# USB_Power.net
KiCad netlist of a schematic drawn in Altium Designer
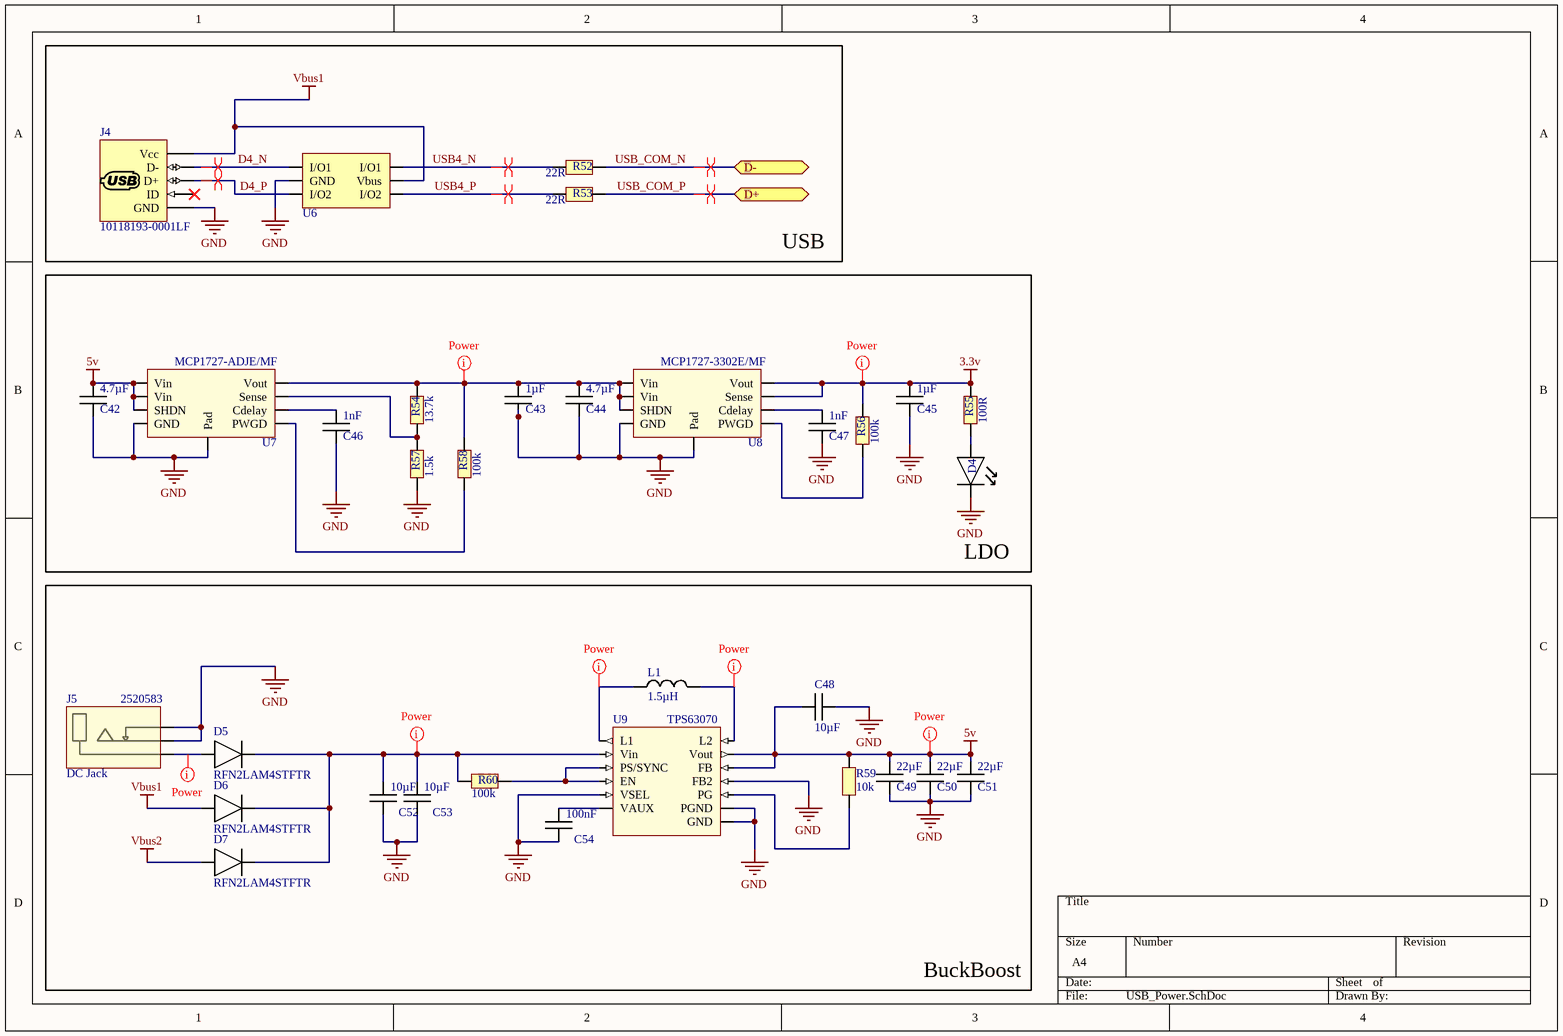
[diagram p0: USB_Power.SchDoc]

(export (version "E")
  (design (tool "Eeschema 10.0.6"))
  (components
    (comp (ref "C42")
      (value "4.7µF")
      (footprint "0603")
      (libsource (lib "Carte_design_SCHLib") (part "Capa"))
    )
    (comp (ref "C43") (value "1µF") (footprint "0603") (libsource (lib "Carte_design_SCHLib") (part "Capa")))
    (comp (ref "C44")
      (value "4.7µF")
      (footprint "0603")
      (libsource (lib "Carte_design_SCHLib") (part "Capa"))
    )
    (comp (ref "C45") (value "1µF") (footprint "0603") (libsource (lib "Carte_design_SCHLib") (part "Capa")))
    (comp (ref "C46") (value "1nF") (footprint "0603") (libsource (lib "Carte_design_SCHLib") (part "Capa")))
    (comp (ref "C47") (value "1nF") (footprint "0603") (libsource (lib "Carte_design_SCHLib") (part "Capa")))
    (comp (ref "C48") (value "10µF") (footprint "0603") (libsource (lib "Carte_design_SCHLib") (part "Capa")))
    (comp (ref "C49") (value "22µF") (footprint "0603") (libsource (lib "Carte_design_SCHLib") (part "Capa")))
    (comp (ref "C50") (value "22µF") (footprint "0603") (libsource (lib "Carte_design_SCHLib") (part "Capa")))
    (comp (ref "C51") (value "22µF") (footprint "0603") (libsource (lib "Carte_design_SCHLib") (part "Capa")))
    (comp (ref "C52") (value "10µF") (footprint "0603") (libsource (lib "Carte_design_SCHLib") (part "Capa")))
    (comp (ref "C53") (value "10µF") (footprint "0603") (libsource (lib "Carte_design_SCHLib") (part "Capa")))
    (comp (ref "C54")
      (value "100nF")
      (footprint "0603")
      (libsource (lib "Carte_design_SCHLib") (part "Capa"))
    )
    (comp (ref "D4")
      (value "Led")
      (footprint "LED_0603")
      (libsource (lib "Carte_design_SCHLib") (part "Led"))
    )
    (comp (ref "D5")
      (value "RFN2LAM4STFTR")
      (footprint "LEd_Pilou")
      (description "RFN2LAM4STF IS THE HIGH RELIABIL")
      (libsource (lib "Carte_design_SCHLib") (part "RFN2LAM4STFTR"))
    )
    (comp (ref "D6")
      (value "RFN2LAM4STFTR")
      (footprint "LEd_Pilou")
      (description "RFN2LAM4STF IS THE HIGH RELIABIL")
      (libsource (lib "Carte_design_SCHLib") (part "RFN2LAM4STFTR"))
    )
    (comp (ref "D7")
      (value "RFN2LAM4STFTR")
      (footprint "LEd_Pilou")
      (description "RFN2LAM4STF IS THE HIGH RELIABIL")
      (libsource (lib "Carte_design_SCHLib") (part "RFN2LAM4STFTR"))
    )
    (comp (ref "J4")
      (value "10118193-0001LF")
      (footprint "Mini_USB_mixte")
      (description "CONN RCPT USB2.0 MICRO B SMD R/A")
      (libsource (lib "Carte_design_SCHLib") (part "10118193-0001LF"))
    )
    (comp (ref "J5")
      (value "DC Jack")
      (footprint "Jack")
      (fields (field (name "SUPPLIER PART NUMBER 1") "2520583"))
      (libsource (lib "Carte_design_SCHLib") (part "Jack"))
    )
    (comp (ref "L1")
      (value "1.5µH")
      (footprint "self_alim")
      (fields (field (name "TOLERANCE") "20%"))
      (libsource (lib "Carte_design_SCHLib") (part "self_alim"))
    )
    (comp (ref "R52") (value "22R") (footprint "0603") (libsource (lib "") (part "Resistance_1")))
    (comp (ref "R53") (value "22R") (footprint "0603") (libsource (lib "") (part "Resistance_1")))
    (comp (ref "R54")
      (value "13.7k")
      (footprint "0603")
      (libsource (lib "Carte_design_SCHLib") (part "Resistance"))
    )
    (comp (ref "R55")
      (value "100R")
      (footprint "0603")
      (libsource (lib "Carte_design_SCHLib") (part "Resistance"))
    )
    (comp (ref "R56")
      (value "100k")
      (footprint "0603")
      (libsource (lib "Carte_design_SCHLib") (part "Resistance"))
    )
    (comp (ref "R57")
      (value "1.5k")
      (footprint "0603")
      (libsource (lib "Carte_design_SCHLib") (part "Resistance"))
    )
    (comp (ref "R58")
      (value "100k")
      (footprint "0603")
      (libsource (lib "Carte_design_SCHLib") (part "Resistance"))
    )
    (comp (ref "R59")
      (value "10k")
      (footprint "0603")
      (libsource (lib "Carte_design_SCHLib") (part "Resistance"))
    )
    (comp (ref "R60") (value "100k") (footprint "0603") (libsource (lib "") (part "Resistance_1")))
    (comp (ref "U6")
      (value "USBLC6-2P6")
      (footprint "SOT95P280X145-6M")
      (description "TVS DIODE 5.25V 17V SOT666")
      (libsource (lib "Carte_design_SCHLib") (part "USBLC6-2P6"))
    )
    (comp (ref "U7")
      (value "MCP1727-ADJE/MF")
      (footprint "PSON65P300X100_HS-9M")
      (libsource (lib "Carte_design_SCHLib") (part "LDO"))
    )
    (comp (ref "U8")
      (value "MCP1727-3302E/MF")
      (footprint "PSON65P300X100_HS-9M")
      (libsource (lib "Carte_design_SCHLib") (part "LDO"))
    )
    (comp (ref "U9")
      (value "TPS63070")
      (footprint "BuckBoost")
      (libsource (lib "Carte_design_SCHLib") (part "12-5V_BuckBoost"))
    )
  )
  (nets
    (net (code "1") (name "/D4_N") (class "Default")
      (node (ref "J4") (pin "2") (pinfunction "D-_2") (pintype "bidirectional"))
      (node (ref "U6") (pin "1") (pinfunction "I/O1_1") (pintype "passive"))
    )
    (net (code "2") (name "/D4_P") (class "Default")
      (node (ref "J4") (pin "3") (pinfunction "D+_3") (pintype "bidirectional"))
      (node (ref "U6") (pin "3") (pinfunction "I/O2_3") (pintype "passive"))
    )
    (net (code "3") (name "/USB4_N") (class "Default")
      (node (ref "R52") (pin "1") (pinfunction "26_1") (pintype "passive"))
      (node (ref "U6") (pin "6") (pinfunction "I/O1_6") (pintype "passive"))
    )
    (net (code "4") (name "/USB4_P") (class "Default")
      (node (ref "R53") (pin "1") (pinfunction "26_1") (pintype "passive"))
      (node (ref "U6") (pin "4") (pinfunction "I/O2_4") (pintype "passive"))
    )
    (net (code "5") (name "/USB_COM_N") (class "Default")
      (node (ref "R52") (pin "2") (pinfunction "27_2") (pintype "passive"))
    )
    (net (code "6") (name "/USB_COM_P") (class "Default")
      (node (ref "R53") (pin "2") (pinfunction "27_2") (pintype "passive"))
    )
    (net (code "7") (name "3.3v") (class "Default")
      (node (ref "C45") (pin "2") (pinfunction "28_2") (pintype "passive"))
      (node (ref "R55") (pin "2") (pinfunction "27_2") (pintype "passive"))
      (node (ref "R56") (pin "2") (pinfunction "27_2") (pintype "passive"))
      (node (ref "U8") (pin "7") (pinfunction "Sense_7") (pintype "passive"))
      (node (ref "U8") (pin "8") (pinfunction "Vout_8") (pintype "passive"))
    )
    (net (code "8") (name "5v") (class "Default")
      (node (ref "C42") (pin "2") (pinfunction "28_2") (pintype "passive"))
      (node (ref "C48") (pin "2") (pinfunction "28_2") (pintype "passive"))
      (node (ref "C49") (pin "2") (pinfunction "28_2") (pintype "passive"))
      (node (ref "C50") (pin "2") (pinfunction "28_2") (pintype "passive"))
      (node (ref "C51") (pin "2") (pinfunction "28_2") (pintype "passive"))
      (node (ref "R59") (pin "2") (pinfunction "27_2") (pintype "passive"))
      (node (ref "U7") (pin "1") (pinfunction "Vin_1") (pintype "passive"))
      (node (ref "U7") (pin "2") (pinfunction "Vin_2") (pintype "passive"))
      (node (ref "U7") (pin "3") (pinfunction "SHDN_3") (pintype "passive"))
      (node (ref "U9") (pin "5") (pinfunction "FB_5") (pintype "input"))
      (node (ref "U9") (pin "7") (pinfunction "Vout_7") (pintype "output"))
    )
    (net (code "9") (name "GND") (class "Default")
      (node (ref "C42") (pin "1") (pinfunction "29_1") (pintype "passive"))
      (node (ref "C43") (pin "1") (pinfunction "29_1") (pintype "passive"))
      (node (ref "C44") (pin "1") (pinfunction "29_1") (pintype "passive"))
      (node (ref "C45") (pin "1") (pinfunction "29_1") (pintype "passive"))
      (node (ref "C46") (pin "1") (pinfunction "29_1") (pintype "passive"))
      (node (ref "C47") (pin "1") (pinfunction "29_1") (pintype "passive"))
      (node (ref "C48") (pin "1") (pinfunction "29_1") (pintype "passive"))
      (node (ref "C49") (pin "1") (pinfunction "29_1") (pintype "passive"))
      (node (ref "C50") (pin "1") (pinfunction "29_1") (pintype "passive"))
      (node (ref "C51") (pin "1") (pinfunction "29_1") (pintype "passive"))
      (node (ref "C52") (pin "1") (pinfunction "29_1") (pintype "passive"))
      (node (ref "C53") (pin "1") (pinfunction "29_1") (pintype "passive"))
      (node (ref "C54") (pin "1") (pinfunction "29_1") (pintype "passive"))
      (node (ref "D4") (pin "2") (pinfunction "31_2") (pintype "passive"))
      (node (ref "J4") (pin "5") (pinfunction "GND_5") (pintype "power_in"))
      (node (ref "J5") (pin "2") (pinfunction "PAD_2") (pintype "passive"))
      (node (ref "J5") (pin "3") (pinfunction "PAD_3") (pintype "passive"))
      (node (ref "R57") (pin "1") (pinfunction "26_1") (pintype "passive"))
      (node (ref "U6") (pin "2") (pinfunction "GND_2") (pintype "passive"))
      (node (ref "U7") (pin "4") (pinfunction "GND_4") (pintype "passive"))
      (node (ref "U7") (pin "9") (pinfunction "Pad_9") (pintype "passive"))
      (node (ref "U8") (pin "4") (pinfunction "GND_4") (pintype "passive"))
      (node (ref "U8") (pin "9") (pinfunction "Pad_9") (pintype "passive"))
      (node (ref "U9") (pin "10") (pinfunction "PGND_10") (pintype "power_in"))
      (node (ref "U9") (pin "15") (pinfunction "VSEL_15") (pintype "input"))
      (node (ref "U9") (pin "4") (pinfunction "GND_4") (pintype "power_in"))
      (node (ref "U9") (pin "6") (pinfunction "FB2_6") (pintype "input"))
    )
    (net (code "10") (name "Net-(C43-28)") (class "Default")
      (node (ref "C43") (pin "2") (pinfunction "28_2") (pintype "passive"))
      (node (ref "C44") (pin "2") (pinfunction "28_2") (pintype "passive"))
      (node (ref "R54") (pin "2") (pinfunction "27_2") (pintype "passive"))
      (node (ref "R58") (pin "2") (pinfunction "27_2") (pintype "passive"))
      (node (ref "U7") (pin "8") (pinfunction "Vout_8") (pintype "passive"))
      (node (ref "U8") (pin "1") (pinfunction "Vin_1") (pintype "passive"))
      (node (ref "U8") (pin "2") (pinfunction "Vin_2") (pintype "passive"))
      (node (ref "U8") (pin "3") (pinfunction "SHDN_3") (pintype "passive"))
    )
    (net (code "11") (name "Net-(C46-28)") (class "Default")
      (node (ref "C46") (pin "2") (pinfunction "28_2") (pintype "passive"))
      (node (ref "U7") (pin "6") (pinfunction "Cdelay_6") (pintype "passive"))
    )
    (net (code "12") (name "Net-(C47-28)") (class "Default")
      (node (ref "C47") (pin "2") (pinfunction "28_2") (pintype "passive"))
      (node (ref "U8") (pin "6") (pinfunction "Cdelay_6") (pintype "passive"))
    )
    (net (code "13") (name "Net-(C52-28)") (class "Default")
      (node (ref "C52") (pin "2") (pinfunction "28_2") (pintype "passive"))
      (node (ref "C53") (pin "2") (pinfunction "28_2") (pintype "passive"))
      (node (ref "D5") (pin "2") (pinfunction "31_2") (pintype "passive"))
      (node (ref "D6") (pin "2") (pinfunction "31_2") (pintype "passive"))
      (node (ref "D7") (pin "2") (pinfunction "31_2") (pintype "passive"))
      (node (ref "R60") (pin "1") (pinfunction "26_1") (pintype "passive"))
      (node (ref "U9") (pin "12") (pinfunction "Vin_12") (pintype "input"))
    )
    (net (code "14") (name "Net-(C54-28)") (class "Default")
      (node (ref "C54") (pin "2") (pinfunction "28_2") (pintype "passive"))
      (node (ref "U9") (pin "3") (pinfunction "VAUX_3") (pintype "passive"))
    )
    (net (code "15") (name "Net-(D4-30)") (class "Default")
      (node (ref "D4") (pin "1") (pinfunction "30_1") (pintype "passive"))
      (node (ref "R55") (pin "1") (pinfunction "26_1") (pintype "passive"))
    )
    (net (code "16") (name "Net-(D5-30)") (class "Default")
      (node (ref "D5") (pin "1") (pinfunction "30_1") (pintype "passive"))
      (node (ref "J5") (pin "1") (pinfunction "PAD_1") (pintype "passive"))
    )
    (net (code "17") (name "Net-(L1-17)") (class "Default")
      (node (ref "L1") (pin "1") (pinfunction "17_1") (pintype "passive"))
      (node (ref "U9") (pin "11") (pinfunction "L1_11") (pintype "output"))
    )
    (net (code "18") (name "Net-(L1-18)") (class "Default")
      (node (ref "L1") (pin "2") (pinfunction "18_2") (pintype "passive"))
      (node (ref "U9") (pin "9") (pinfunction "L2_9") (pintype "input"))
    )
    (net (code "19") (name "Net-(R54-26)") (class "Default")
      (node (ref "R54") (pin "1") (pinfunction "26_1") (pintype "passive"))
      (node (ref "R57") (pin "2") (pinfunction "27_2") (pintype "passive"))
      (node (ref "U7") (pin "7") (pinfunction "Sense_7") (pintype "passive"))
    )
    (net (code "20") (name "Net-(R56-26)") (class "Default")
      (node (ref "R56") (pin "1") (pinfunction "26_1") (pintype "passive"))
      (node (ref "U8") (pin "5") (pinfunction "PWGD_5") (pintype "passive"))
    )
    (net (code "21") (name "Net-(R58-26)") (class "Default")
      (node (ref "R58") (pin "1") (pinfunction "26_1") (pintype "passive"))
      (node (ref "U7") (pin "5") (pinfunction "PWGD_5") (pintype "passive"))
    )
    (net (code "22") (name "Net-(R59-26)") (class "Default")
      (node (ref "R59") (pin "1") (pinfunction "26_1") (pintype "passive"))
      (node (ref "U9") (pin "2") (pinfunction "PG_2") (pintype "input"))
    )
    (net (code "23") (name "Net-(R60-27)") (class "Default")
      (node (ref "R60") (pin "2") (pinfunction "27_2") (pintype "passive"))
      (node (ref "U9") (pin "1") (pinfunction "PS/SYNC_1") (pintype "input"))
      (node (ref "U9") (pin "14") (pinfunction "EN_14") (pintype "input"))
    )
    (net (code "24") (name "Vbus1") (class "Default")
      (node (ref "D6") (pin "1") (pinfunction "30_1") (pintype "passive"))
      (node (ref "J4") (pin "1") (pinfunction "Vcc_1") (pintype "power_in"))
      (node (ref "U6") (pin "5") (pinfunction "Vbus_5") (pintype "passive"))
    )
    (net (code "25") (name "Vbus2") (class "Default")
      (node (ref "D7") (pin "1") (pinfunction "30_1") (pintype "passive"))
    )
    (net (code "26") (name "unconnected-(J4-ID-Pad4)") (class "Default")
      (node (ref "J4") (pin "4") (pinfunction "ID_4") (pintype "input+no_connect"))
    )
  )
)
